# keyboard-8.net
KiCad netlist of a schematic drawn in EAGLE
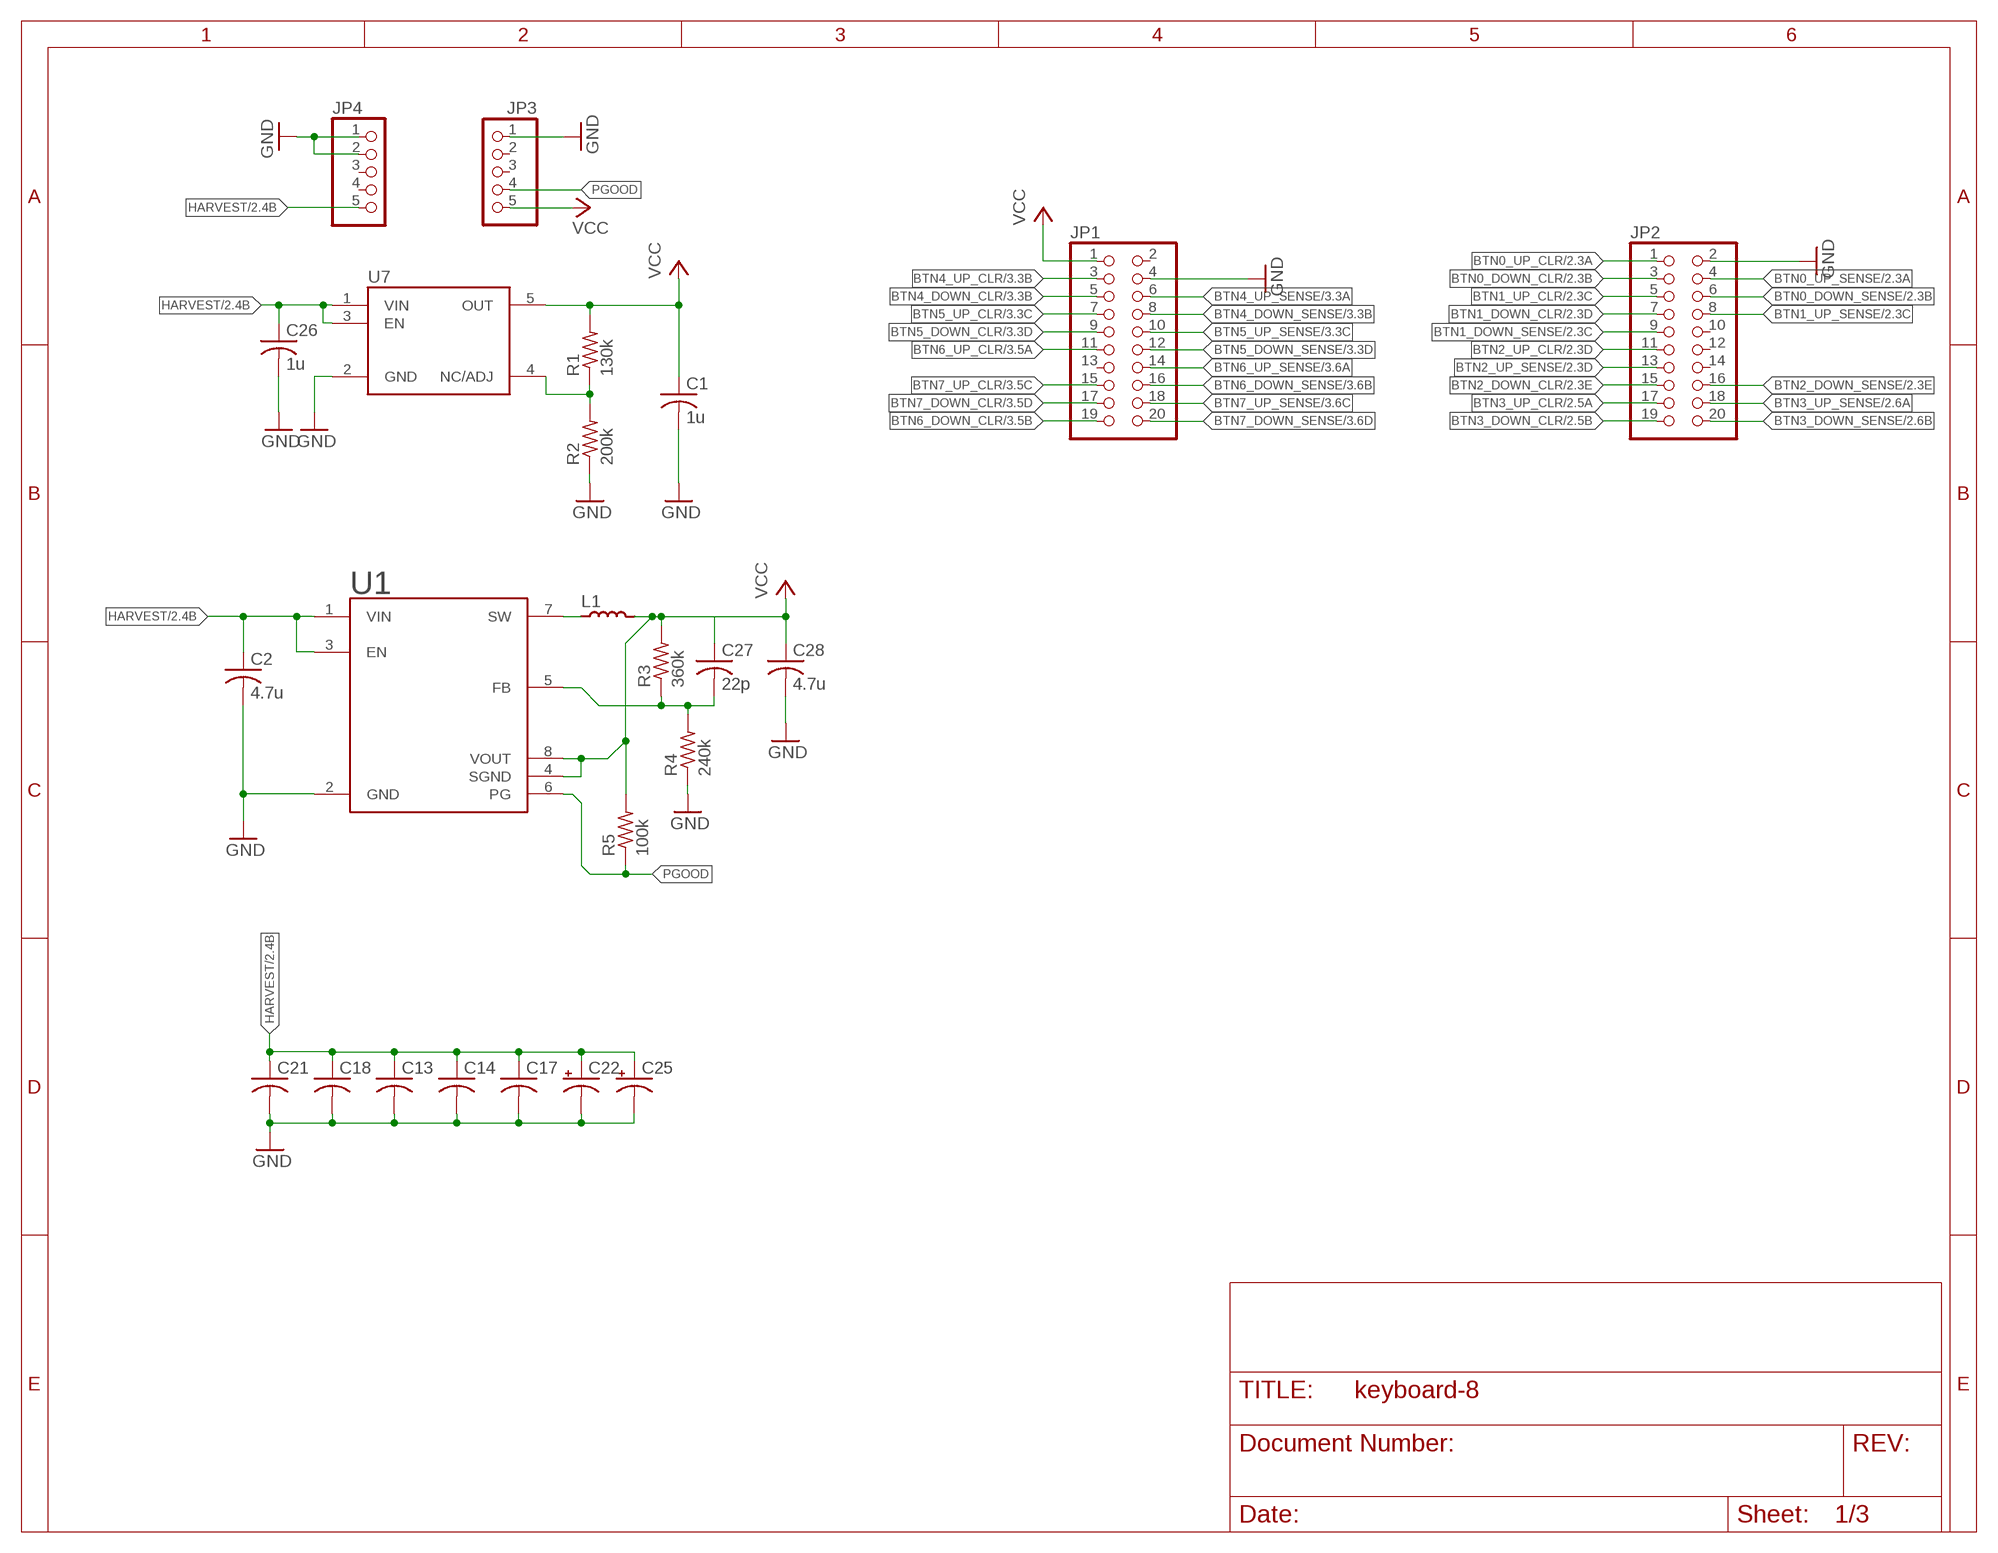
[diagram p0: schematic, sheet 1]
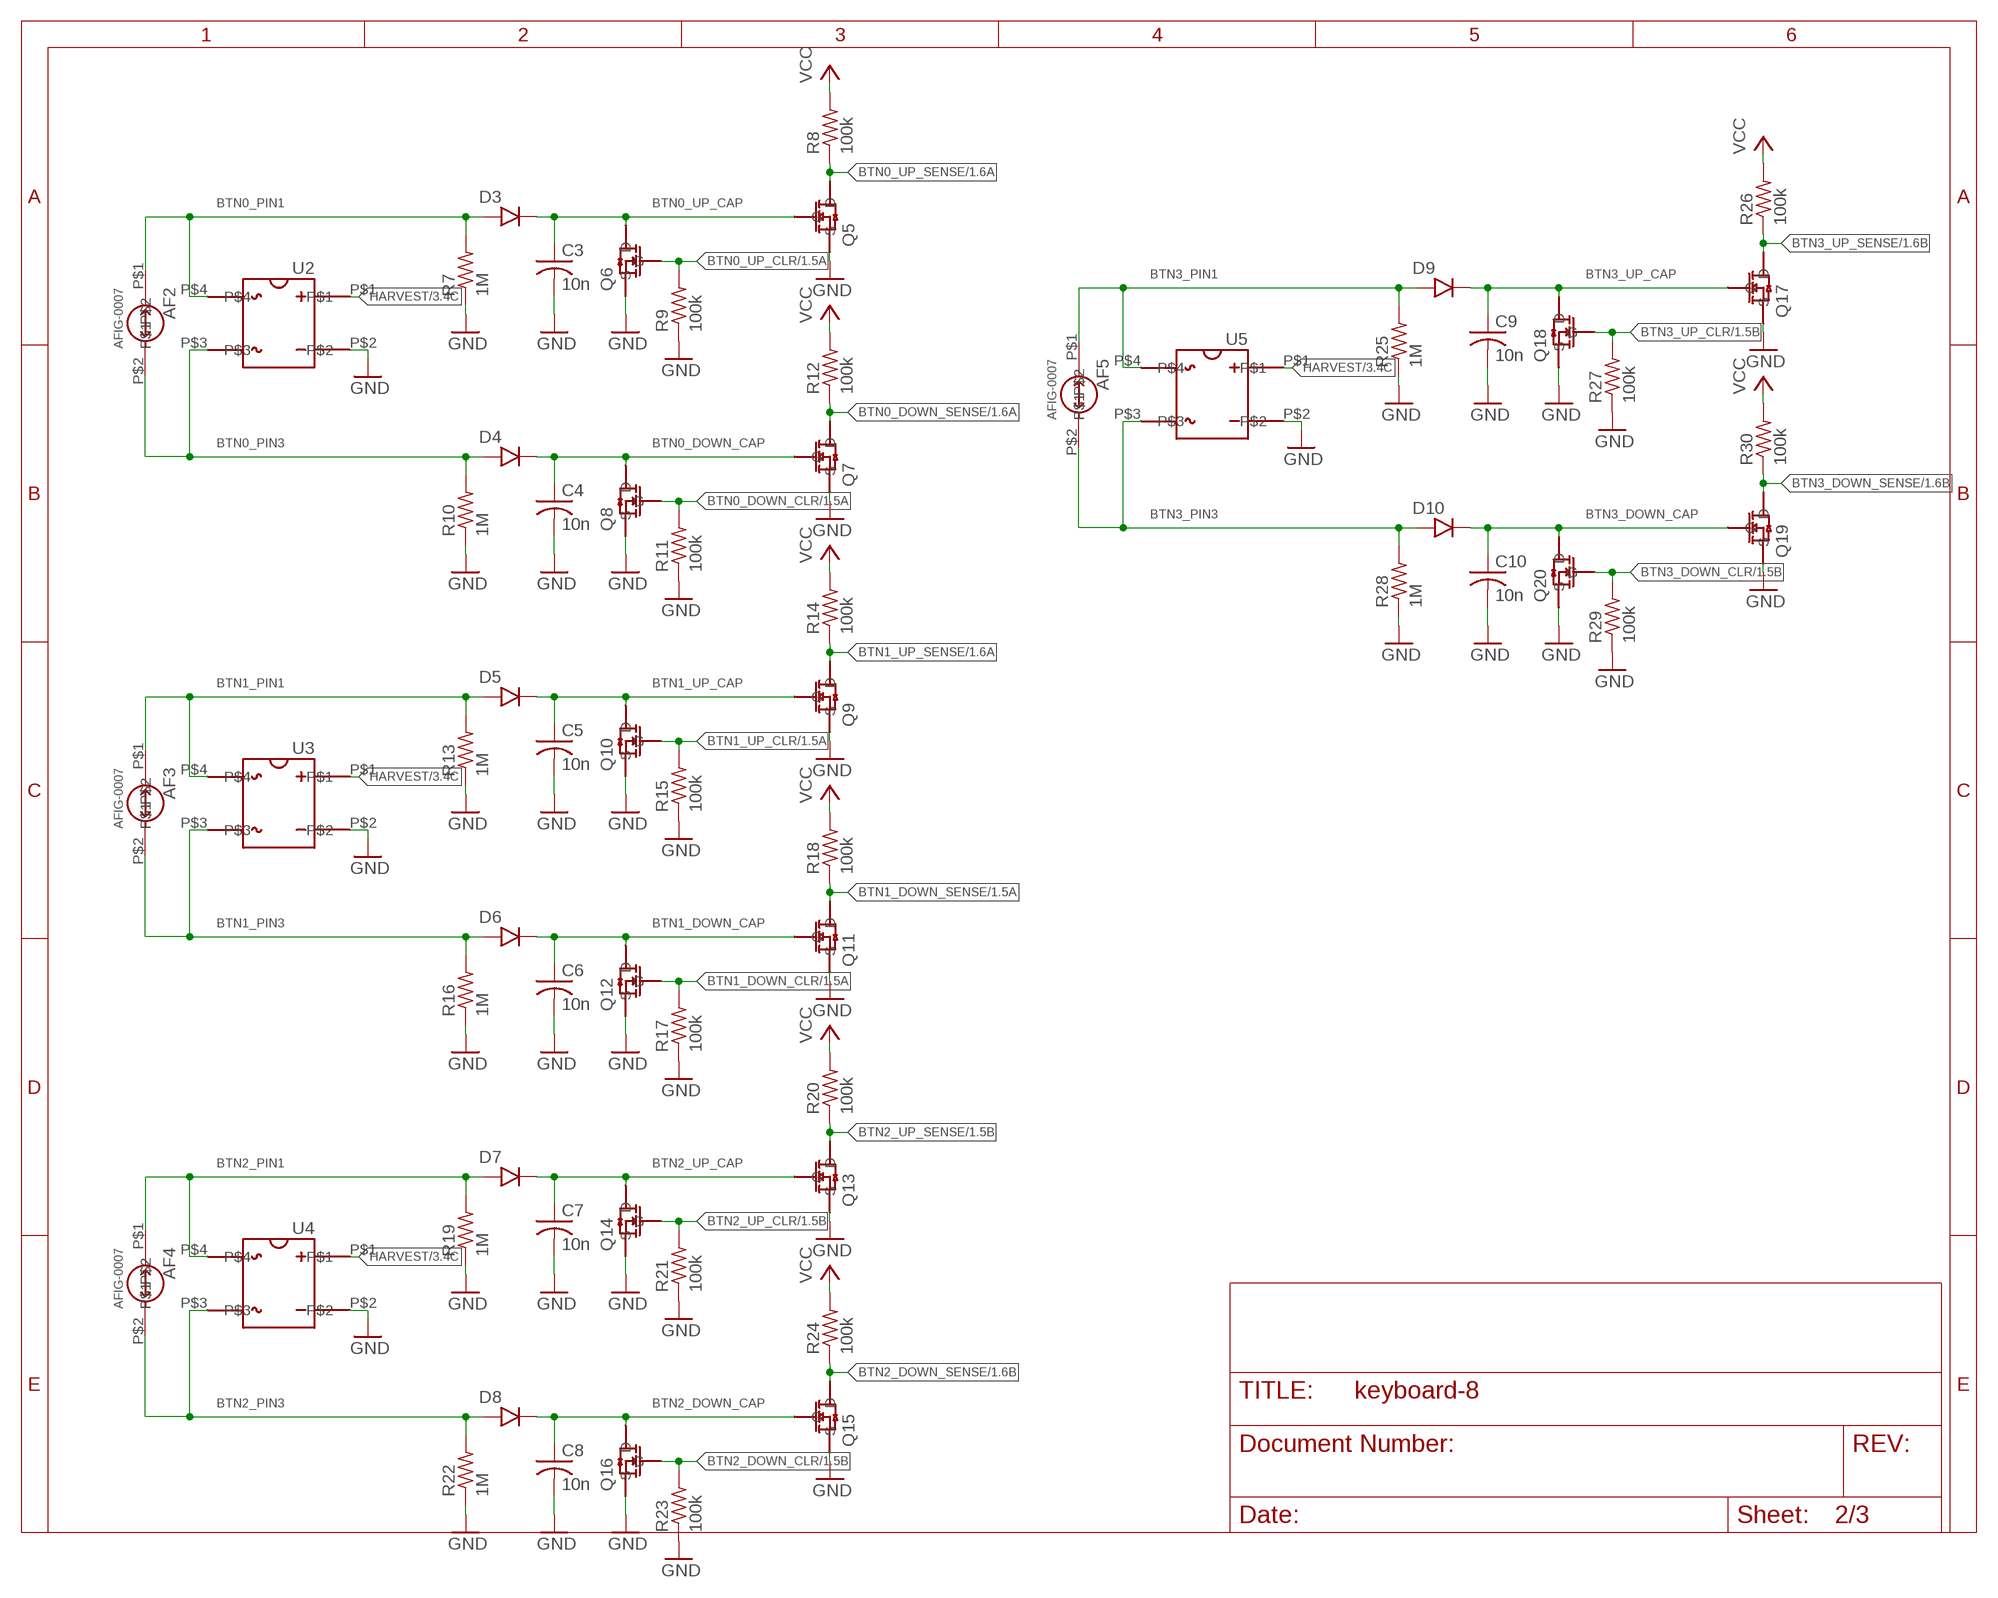
[diagram p1: schematic, sheet 2]
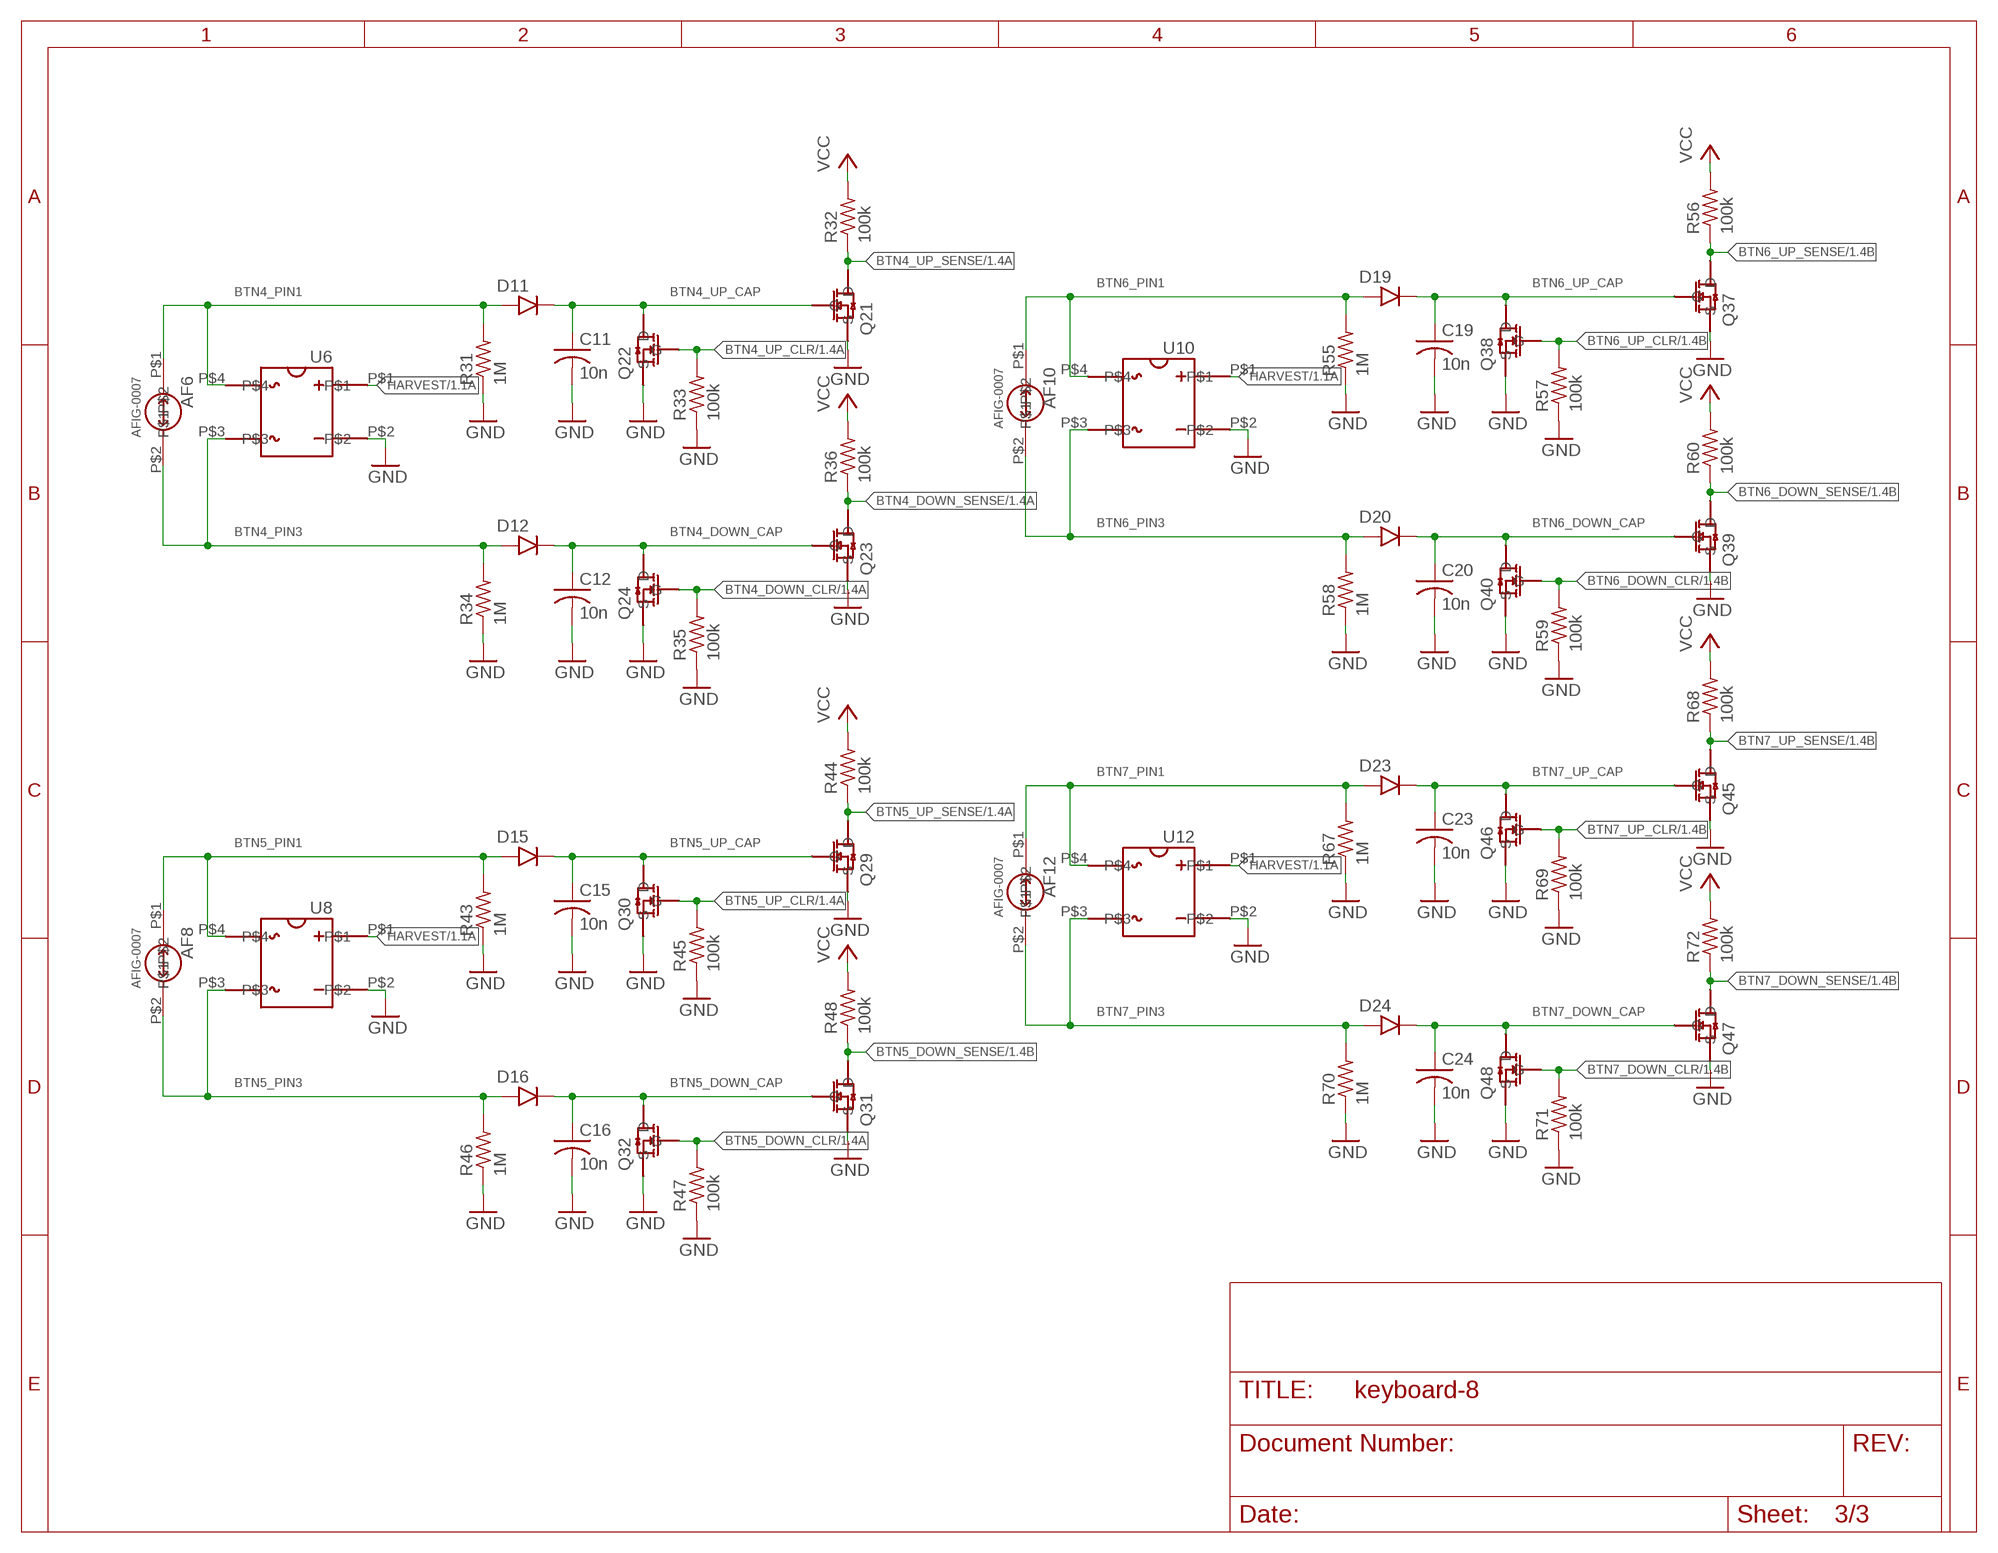
[diagram p2: schematic, sheet 3]

(export (version "E")
  (design (tool "Eeschema 10.0.6"))
  (components
    (comp (ref "C1")
      (value "1u")
      (footprint "eagle-import:C0402")
      (libsource (lib "eagle-import") (part "C-USC0402"))
    )
    (comp (ref "C2")
      (value "4.7u")
      (footprint "eagle-import:C0603")
      (libsource (lib "eagle-import") (part "C-USC0603"))
    )
    (comp (ref "C13")
      (value "C-USC1206")
      (footprint "eagle-import:C1206")
      (libsource (lib "eagle-import") (part "C-USC1206"))
    )
    (comp (ref "C14")
      (value "C-USC1206")
      (footprint "eagle-import:C1206")
      (libsource (lib "eagle-import") (part "C-USC1206"))
    )
    (comp (ref "C17")
      (value "C-USC1206")
      (footprint "eagle-import:C1206")
      (libsource (lib "eagle-import") (part "C-USC1206"))
    )
    (comp (ref "C18")
      (value "C-USC0805")
      (footprint "eagle-import:C0805")
      (libsource (lib "eagle-import") (part "C-USC0805"))
    )
    (comp (ref "C21")
      (value "C-USC0805")
      (footprint "eagle-import:C0805")
      (libsource (lib "eagle-import") (part "C-USC0805"))
    )
    (comp (ref "C22")
      (value "CPOL-USE2-5")
      (footprint "eagle-import:E2-5")
      (libsource (lib "eagle-import") (part "CPOL-USE2-5"))
    )
    (comp (ref "C25")
      (value "CPOL-USE2-5")
      (footprint "eagle-import:E2-5")
      (libsource (lib "eagle-import") (part "CPOL-USE2-5"))
    )
    (comp (ref "C26")
      (value "1u")
      (footprint "eagle-import:C0402")
      (libsource (lib "eagle-import") (part "C-USC0402"))
    )
    (comp (ref "C27")
      (value "22p")
      (footprint "eagle-import:C0402")
      (libsource (lib "eagle-import") (part "C-USC0402"))
    )
    (comp (ref "C28")
      (value "4.7u")
      (footprint "eagle-import:C0603")
      (libsource (lib "eagle-import") (part "C-USC0603"))
    )
    (comp (ref "JP1")
      (value "PINHD-2X10")
      (footprint "eagle-import:2X10")
      (libsource (lib "eagle-import") (part "PINHD-2X10"))
    )
    (comp (ref "JP2")
      (value "PINHD-2X10")
      (footprint "eagle-import:2X10")
      (libsource (lib "eagle-import") (part "PINHD-2X10"))
    )
    (comp (ref "JP3")
      (value "PINHD-1X5")
      (footprint "eagle-import:1X05")
      (libsource (lib "eagle-import") (part "PINHD-1X5"))
    )
    (comp (ref "JP4")
      (value "PINHD-1X5")
      (footprint "eagle-import:1X05")
      (libsource (lib "eagle-import") (part "PINHD-1X5"))
    )
    (comp (ref "L1")
      (value "22u")
      (footprint "eagle-import:LQH3NPNXXXXMEX")
      (libsource (lib "eagle-import") (part "LQH3NPN220MMEL"))
    )
    (comp (ref "R1")
      (value "130k")
      (footprint "eagle-import:R0603")
      (libsource (lib "eagle-import") (part "R-US_R0603"))
    )
    (comp (ref "R2")
      (value "200k")
      (footprint "eagle-import:R0603")
      (libsource (lib "eagle-import") (part "R-US_R0603"))
    )
    (comp (ref "R3")
      (value "360k")
      (footprint "eagle-import:R0402")
      (libsource (lib "eagle-import") (part "R-US_R0402"))
    )
    (comp (ref "R4")
      (value "240k")
      (footprint "eagle-import:R0402")
      (libsource (lib "eagle-import") (part "R-US_R0402"))
    )
    (comp (ref "R5")
      (value "100k")
      (footprint "eagle-import:R0402")
      (libsource (lib "eagle-import") (part "R-US_R0402"))
    )
    (comp (ref "U1")
      (value "TPS62120")
      (footprint "eagle-import:SOP65P280X145-8N")
      (libsource (lib "eagle-import") (part "TPS62120"))
    )
    (comp (ref "U7")
      (value "MIC5225")
      (footprint "eagle-import:MIC5225")
      (libsource (lib "eagle-import") (part "MIC5225"))
    )
    (comp (ref "AF6")
      (value "BUTTON-MOUNT")
      (footprint "eagle-import:BUTTON-MOUNT")
      (libsource (lib "eagle-import") (part "BUTTON-MOUNT"))
    )
    (comp (ref "AF8")
      (value "BUTTON-MOUNT")
      (footprint "eagle-import:BUTTON-MOUNT")
      (libsource (lib "eagle-import") (part "BUTTON-MOUNT"))
    )
    (comp (ref "AF10")
      (value "BUTTON-MOUNT")
      (footprint "eagle-import:BUTTON-MOUNT")
      (libsource (lib "eagle-import") (part "BUTTON-MOUNT"))
    )
    (comp (ref "AF12")
      (value "BUTTON-MOUNT")
      (footprint "eagle-import:BUTTON-MOUNT")
      (libsource (lib "eagle-import") (part "BUTTON-MOUNT"))
    )
    (comp (ref "C11")
      (value "10n")
      (footprint "eagle-import:C0402")
      (libsource (lib "eagle-import") (part "C-USC0402"))
    )
    (comp (ref "C12")
      (value "10n")
      (footprint "eagle-import:C0402")
      (libsource (lib "eagle-import") (part "C-USC0402"))
    )
    (comp (ref "C15")
      (value "10n")
      (footprint "eagle-import:C0402")
      (libsource (lib "eagle-import") (part "C-USC0402"))
    )
    (comp (ref "C16")
      (value "10n")
      (footprint "eagle-import:C0402")
      (libsource (lib "eagle-import") (part "C-USC0402"))
    )
    (comp (ref "C19")
      (value "10n")
      (footprint "eagle-import:C0402")
      (libsource (lib "eagle-import") (part "C-USC0402"))
    )
    (comp (ref "C20")
      (value "10n")
      (footprint "eagle-import:C0402")
      (libsource (lib "eagle-import") (part "C-USC0402"))
    )
    (comp (ref "C23")
      (value "10n")
      (footprint "eagle-import:C0402")
      (libsource (lib "eagle-import") (part "C-USC0402"))
    )
    (comp (ref "C24")
      (value "10n")
      (footprint "eagle-import:C0402")
      (libsource (lib "eagle-import") (part "C-USC0402"))
    )
    (comp (ref "D11")
      (value "DFLU1200")
      (footprint "eagle-import:DFLU1200")
      (libsource (lib "eagle-import") (part "DFLU1200"))
    )
    (comp (ref "D12")
      (value "DFLU1200")
      (footprint "eagle-import:DFLU1200")
      (libsource (lib "eagle-import") (part "DFLU1200"))
    )
    (comp (ref "D15")
      (value "DFLU1200")
      (footprint "eagle-import:DFLU1200")
      (libsource (lib "eagle-import") (part "DFLU1200"))
    )
    (comp (ref "D16")
      (value "DFLU1200")
      (footprint "eagle-import:DFLU1200")
      (libsource (lib "eagle-import") (part "DFLU1200"))
    )
    (comp (ref "D19")
      (value "DFLU1200")
      (footprint "eagle-import:DFLU1200")
      (libsource (lib "eagle-import") (part "DFLU1200"))
    )
    (comp (ref "D20")
      (value "DFLU1200")
      (footprint "eagle-import:DFLU1200")
      (libsource (lib "eagle-import") (part "DFLU1200"))
    )
    (comp (ref "D23")
      (value "DFLU1200")
      (footprint "eagle-import:DFLU1200")
      (libsource (lib "eagle-import") (part "DFLU1200"))
    )
    (comp (ref "D24")
      (value "DFLU1200")
      (footprint "eagle-import:DFLU1200")
      (libsource (lib "eagle-import") (part "DFLU1200"))
    )
    (comp (ref "Q21")
      (value "2N7002K-7")
      (footprint "eagle-import:2N7002K-7")
      (libsource (lib "eagle-import") (part "2N7002K-7"))
    )
    (comp (ref "Q22")
      (value "BSS138K")
      (footprint "eagle-import:BSS138K")
      (libsource (lib "eagle-import") (part "BSS138K"))
    )
    (comp (ref "Q23")
      (value "2N7002K-7")
      (footprint "eagle-import:2N7002K-7")
      (libsource (lib "eagle-import") (part "2N7002K-7"))
    )
    (comp (ref "Q24")
      (value "BSS138K")
      (footprint "eagle-import:BSS138K")
      (libsource (lib "eagle-import") (part "BSS138K"))
    )
    (comp (ref "Q29")
      (value "2N7002K-7")
      (footprint "eagle-import:2N7002K-7")
      (libsource (lib "eagle-import") (part "2N7002K-7"))
    )
    (comp (ref "Q30")
      (value "BSS138K")
      (footprint "eagle-import:BSS138K")
      (libsource (lib "eagle-import") (part "BSS138K"))
    )
    (comp (ref "Q31")
      (value "2N7002K-7")
      (footprint "eagle-import:2N7002K-7")
      (libsource (lib "eagle-import") (part "2N7002K-7"))
    )
    (comp (ref "Q32")
      (value "BSS138K")
      (footprint "eagle-import:BSS138K")
      (libsource (lib "eagle-import") (part "BSS138K"))
    )
    (comp (ref "Q37")
      (value "2N7002K-7")
      (footprint "eagle-import:2N7002K-7")
      (libsource (lib "eagle-import") (part "2N7002K-7"))
    )
    (comp (ref "Q38")
      (value "BSS138K")
      (footprint "eagle-import:BSS138K")
      (libsource (lib "eagle-import") (part "BSS138K"))
    )
    (comp (ref "Q39")
      (value "2N7002K-7")
      (footprint "eagle-import:2N7002K-7")
      (libsource (lib "eagle-import") (part "2N7002K-7"))
    )
    (comp (ref "Q40")
      (value "BSS138K")
      (footprint "eagle-import:BSS138K")
      (libsource (lib "eagle-import") (part "BSS138K"))
    )
    (comp (ref "Q45")
      (value "2N7002K-7")
      (footprint "eagle-import:2N7002K-7")
      (libsource (lib "eagle-import") (part "2N7002K-7"))
    )
    (comp (ref "Q46")
      (value "BSS138K")
      (footprint "eagle-import:BSS138K")
      (libsource (lib "eagle-import") (part "BSS138K"))
    )
    (comp (ref "Q47")
      (value "2N7002K-7")
      (footprint "eagle-import:2N7002K-7")
      (libsource (lib "eagle-import") (part "2N7002K-7"))
    )
    (comp (ref "Q48")
      (value "BSS138K")
      (footprint "eagle-import:BSS138K")
      (libsource (lib "eagle-import") (part "BSS138K"))
    )
    (comp (ref "R31")
      (value "1M")
      (footprint "eagle-import:R0402")
      (libsource (lib "eagle-import") (part "R-US_R0402"))
    )
    (comp (ref "R32")
      (value "100k")
      (footprint "eagle-import:R0402")
      (libsource (lib "eagle-import") (part "R-US_R0402"))
    )
    (comp (ref "R33")
      (value "100k")
      (footprint "eagle-import:R0402")
      (libsource (lib "eagle-import") (part "R-US_R0402"))
    )
    (comp (ref "R34")
      (value "1M")
      (footprint "eagle-import:R0402")
      (libsource (lib "eagle-import") (part "R-US_R0402"))
    )
    (comp (ref "R35")
      (value "100k")
      (footprint "eagle-import:R0402")
      (libsource (lib "eagle-import") (part "R-US_R0402"))
    )
    (comp (ref "R36")
      (value "100k")
      (footprint "eagle-import:R0402")
      (libsource (lib "eagle-import") (part "R-US_R0402"))
    )
    (comp (ref "R43")
      (value "1M")
      (footprint "eagle-import:R0402")
      (libsource (lib "eagle-import") (part "R-US_R0402"))
    )
    (comp (ref "R44")
      (value "100k")
      (footprint "eagle-import:R0402")
      (libsource (lib "eagle-import") (part "R-US_R0402"))
    )
    (comp (ref "R45")
      (value "100k")
      (footprint "eagle-import:R0402")
      (libsource (lib "eagle-import") (part "R-US_R0402"))
    )
    (comp (ref "R46")
      (value "1M")
      (footprint "eagle-import:R0402")
      (libsource (lib "eagle-import") (part "R-US_R0402"))
    )
    (comp (ref "R47")
      (value "100k")
      (footprint "eagle-import:R0402")
      (libsource (lib "eagle-import") (part "R-US_R0402"))
    )
    (comp (ref "R48")
      (value "100k")
      (footprint "eagle-import:R0402")
      (libsource (lib "eagle-import") (part "R-US_R0402"))
    )
    (comp (ref "R55")
      (value "1M")
      (footprint "eagle-import:R0402")
      (libsource (lib "eagle-import") (part "R-US_R0402"))
    )
    (comp (ref "R56")
      (value "100k")
      (footprint "eagle-import:R0402")
      (libsource (lib "eagle-import") (part "R-US_R0402"))
    )
    (comp (ref "R57")
      (value "100k")
      (footprint "eagle-import:R0402")
      (libsource (lib "eagle-import") (part "R-US_R0402"))
    )
    (comp (ref "R58")
      (value "1M")
      (footprint "eagle-import:R0402")
      (libsource (lib "eagle-import") (part "R-US_R0402"))
    )
    (comp (ref "R59")
      (value "100k")
      (footprint "eagle-import:R0402")
      (libsource (lib "eagle-import") (part "R-US_R0402"))
    )
    (comp (ref "R60")
      (value "100k")
      (footprint "eagle-import:R0402")
      (libsource (lib "eagle-import") (part "R-US_R0402"))
    )
    (comp (ref "R67")
      (value "1M")
      (footprint "eagle-import:R0402")
      (libsource (lib "eagle-import") (part "R-US_R0402"))
    )
    (comp (ref "R68")
      (value "100k")
      (footprint "eagle-import:R0402")
      (libsource (lib "eagle-import") (part "R-US_R0402"))
    )
    (comp (ref "R69")
      (value "100k")
      (footprint "eagle-import:R0402")
      (libsource (lib "eagle-import") (part "R-US_R0402"))
    )
    (comp (ref "R70")
      (value "1M")
      (footprint "eagle-import:R0402")
      (libsource (lib "eagle-import") (part "R-US_R0402"))
    )
    (comp (ref "R71")
      (value "100k")
      (footprint "eagle-import:R0402")
      (libsource (lib "eagle-import") (part "R-US_R0402"))
    )
    (comp (ref "R72")
      (value "100k")
      (footprint "eagle-import:R0402")
      (libsource (lib "eagle-import") (part "R-US_R0402"))
    )
    (comp (ref "U6")
      (value "CDBHD140L-G")
      (footprint "eagle-import:CDBHDXX0L-G")
      (libsource (lib "eagle-import") (part "CDBHD140L-G"))
    )
    (comp (ref "U8")
      (value "CDBHD140L-G")
      (footprint "eagle-import:CDBHDXX0L-G")
      (libsource (lib "eagle-import") (part "CDBHD140L-G"))
    )
    (comp (ref "U10")
      (value "CDBHD140L-G")
      (footprint "eagle-import:CDBHDXX0L-G")
      (libsource (lib "eagle-import") (part "CDBHD140L-G"))
    )
    (comp (ref "U12")
      (value "CDBHD140L-G")
      (footprint "eagle-import:CDBHDXX0L-G")
      (libsource (lib "eagle-import") (part "CDBHD140L-G"))
    )
    (comp (ref "AF2")
      (value "BUTTON-MOUNT")
      (footprint "eagle-import:BUTTON-MOUNT")
      (libsource (lib "eagle-import") (part "BUTTON-MOUNT"))
    )
    (comp (ref "AF3")
      (value "BUTTON-MOUNT")
      (footprint "eagle-import:BUTTON-MOUNT")
      (libsource (lib "eagle-import") (part "BUTTON-MOUNT"))
    )
    (comp (ref "AF4")
      (value "BUTTON-MOUNT")
      (footprint "eagle-import:BUTTON-MOUNT")
      (libsource (lib "eagle-import") (part "BUTTON-MOUNT"))
    )
    (comp (ref "AF5")
      (value "BUTTON-MOUNT")
      (footprint "eagle-import:BUTTON-MOUNT")
      (libsource (lib "eagle-import") (part "BUTTON-MOUNT"))
    )
    (comp (ref "C3")
      (value "10n")
      (footprint "eagle-import:C0402")
      (libsource (lib "eagle-import") (part "C-USC0402"))
    )
    (comp (ref "C4")
      (value "10n")
      (footprint "eagle-import:C0402")
      (libsource (lib "eagle-import") (part "C-USC0402"))
    )
    (comp (ref "C5")
      (value "10n")
      (footprint "eagle-import:C0402")
      (libsource (lib "eagle-import") (part "C-USC0402"))
    )
    (comp (ref "C6")
      (value "10n")
      (footprint "eagle-import:C0402")
      (libsource (lib "eagle-import") (part "C-USC0402"))
    )
    (comp (ref "C7")
      (value "10n")
      (footprint "eagle-import:C0402")
      (libsource (lib "eagle-import") (part "C-USC0402"))
    )
    (comp (ref "C8")
      (value "10n")
      (footprint "eagle-import:C0402")
      (libsource (lib "eagle-import") (part "C-USC0402"))
    )
    (comp (ref "C9")
      (value "10n")
      (footprint "eagle-import:C0402")
      (libsource (lib "eagle-import") (part "C-USC0402"))
    )
    (comp (ref "C10")
      (value "10n")
      (footprint "eagle-import:C0402")
      (libsource (lib "eagle-import") (part "C-USC0402"))
    )
    (comp (ref "D3")
      (value "DFLU1200")
      (footprint "eagle-import:DFLU1200")
      (libsource (lib "eagle-import") (part "DFLU1200"))
    )
    (comp (ref "D4")
      (value "DFLU1200")
      (footprint "eagle-import:DFLU1200")
      (libsource (lib "eagle-import") (part "DFLU1200"))
    )
    (comp (ref "D5")
      (value "DFLU1200")
      (footprint "eagle-import:DFLU1200")
      (libsource (lib "eagle-import") (part "DFLU1200"))
    )
    (comp (ref "D6")
      (value "DFLU1200")
      (footprint "eagle-import:DFLU1200")
      (libsource (lib "eagle-import") (part "DFLU1200"))
    )
    (comp (ref "D7")
      (value "DFLU1200")
      (footprint "eagle-import:DFLU1200")
      (libsource (lib "eagle-import") (part "DFLU1200"))
    )
    (comp (ref "D8")
      (value "DFLU1200")
      (footprint "eagle-import:DFLU1200")
      (libsource (lib "eagle-import") (part "DFLU1200"))
    )
    (comp (ref "D9")
      (value "DFLU1200")
      (footprint "eagle-import:DFLU1200")
      (libsource (lib "eagle-import") (part "DFLU1200"))
    )
    (comp (ref "D10")
      (value "DFLU1200")
      (footprint "eagle-import:DFLU1200")
      (libsource (lib "eagle-import") (part "DFLU1200"))
    )
    (comp (ref "Q5")
      (value "2N7002K-7")
      (footprint "eagle-import:2N7002K-7")
      (libsource (lib "eagle-import") (part "2N7002K-7"))
    )
    (comp (ref "Q6")
      (value "BSS138K")
      (footprint "eagle-import:BSS138K")
      (libsource (lib "eagle-import") (part "BSS138K"))
    )
    (comp (ref "Q7")
      (value "2N7002K-7")
      (footprint "eagle-import:2N7002K-7")
      (libsource (lib "eagle-import") (part "2N7002K-7"))
    )
    (comp (ref "Q8")
      (value "BSS138K")
      (footprint "eagle-import:BSS138K")
      (libsource (lib "eagle-import") (part "BSS138K"))
    )
    (comp (ref "Q9")
      (value "2N7002K-7")
      (footprint "eagle-import:2N7002K-7")
      (libsource (lib "eagle-import") (part "2N7002K-7"))
    )
    (comp (ref "Q10")
      (value "BSS138K")
      (footprint "eagle-import:BSS138K")
      (libsource (lib "eagle-import") (part "BSS138K"))
    )
    (comp (ref "Q11")
      (value "2N7002K-7")
      (footprint "eagle-import:2N7002K-7")
      (libsource (lib "eagle-import") (part "2N7002K-7"))
    )
    (comp (ref "Q12")
      (value "BSS138K")
      (footprint "eagle-import:BSS138K")
      (libsource (lib "eagle-import") (part "BSS138K"))
    )
    (comp (ref "Q13")
      (value "2N7002K-7")
      (footprint "eagle-import:2N7002K-7")
      (libsource (lib "eagle-import") (part "2N7002K-7"))
    )
    (comp (ref "Q14")
      (value "BSS138K")
      (footprint "eagle-import:BSS138K")
      (libsource (lib "eagle-import") (part "BSS138K"))
    )
    (comp (ref "Q15")
      (value "2N7002K-7")
      (footprint "eagle-import:2N7002K-7")
      (libsource (lib "eagle-import") (part "2N7002K-7"))
    )
    (comp (ref "Q16")
      (value "BSS138K")
      (footprint "eagle-import:BSS138K")
      (libsource (lib "eagle-import") (part "BSS138K"))
    )
    (comp (ref "Q17")
      (value "2N7002K-7")
      (footprint "eagle-import:2N7002K-7")
      (libsource (lib "eagle-import") (part "2N7002K-7"))
    )
    (comp (ref "Q18")
      (value "BSS138K")
      (footprint "eagle-import:BSS138K")
      (libsource (lib "eagle-import") (part "BSS138K"))
    )
    (comp (ref "Q19")
      (value "2N7002K-7")
      (footprint "eagle-import:2N7002K-7")
      (libsource (lib "eagle-import") (part "2N7002K-7"))
    )
    (comp (ref "Q20")
      (value "BSS138K")
      (footprint "eagle-import:BSS138K")
      (libsource (lib "eagle-import") (part "BSS138K"))
    )
    (comp (ref "R7")
      (value "1M")
      (footprint "eagle-import:R0402")
      (libsource (lib "eagle-import") (part "R-US_R0402"))
    )
    (comp (ref "R8")
      (value "100k")
      (footprint "eagle-import:R0402")
      (libsource (lib "eagle-import") (part "R-US_R0402"))
    )
    (comp (ref "R9")
      (value "100k")
      (footprint "eagle-import:R0402")
      (libsource (lib "eagle-import") (part "R-US_R0402"))
    )
    (comp (ref "R10")
      (value "1M")
      (footprint "eagle-import:R0402")
      (libsource (lib "eagle-import") (part "R-US_R0402"))
    )
    (comp (ref "R11")
      (value "100k")
      (footprint "eagle-import:R0402")
      (libsource (lib "eagle-import") (part "R-US_R0402"))
    )
    (comp (ref "R12")
      (value "100k")
      (footprint "eagle-import:R0402")
      (libsource (lib "eagle-import") (part "R-US_R0402"))
    )
    (comp (ref "R13")
      (value "1M")
      (footprint "eagle-import:R0402")
      (libsource (lib "eagle-import") (part "R-US_R0402"))
    )
    (comp (ref "R14")
      (value "100k")
      (footprint "eagle-import:R0402")
      (libsource (lib "eagle-import") (part "R-US_R0402"))
    )
    (comp (ref "R15")
      (value "100k")
      (footprint "eagle-import:R0402")
      (libsource (lib "eagle-import") (part "R-US_R0402"))
    )
    (comp (ref "R16")
      (value "1M")
      (footprint "eagle-import:R0402")
      (libsource (lib "eagle-import") (part "R-US_R0402"))
    )
    (comp (ref "R17")
      (value "100k")
      (footprint "eagle-import:R0402")
      (libsource (lib "eagle-import") (part "R-US_R0402"))
    )
    (comp (ref "R18")
      (value "100k")
      (footprint "eagle-import:R0402")
      (libsource (lib "eagle-import") (part "R-US_R0402"))
    )
    (comp (ref "R19")
      (value "1M")
      (footprint "eagle-import:R0402")
      (libsource (lib "eagle-import") (part "R-US_R0402"))
    )
    (comp (ref "R20")
      (value "100k")
      (footprint "eagle-import:R0402")
      (libsource (lib "eagle-import") (part "R-US_R0402"))
    )
    (comp (ref "R21")
      (value "100k")
      (footprint "eagle-import:R0402")
      (libsource (lib "eagle-import") (part "R-US_R0402"))
    )
    (comp (ref "R22")
      (value "1M")
      (footprint "eagle-import:R0402")
      (libsource (lib "eagle-import") (part "R-US_R0402"))
    )
    (comp (ref "R23")
      (value "100k")
      (footprint "eagle-import:R0402")
      (libsource (lib "eagle-import") (part "R-US_R0402"))
    )
    (comp (ref "R24")
      (value "100k")
      (footprint "eagle-import:R0402")
      (libsource (lib "eagle-import") (part "R-US_R0402"))
    )
    (comp (ref "R25")
      (value "1M")
      (footprint "eagle-import:R0402")
      (libsource (lib "eagle-import") (part "R-US_R0402"))
    )
    (comp (ref "R26")
      (value "100k")
      (footprint "eagle-import:R0402")
      (libsource (lib "eagle-import") (part "R-US_R0402"))
    )
    (comp (ref "R27")
      (value "100k")
      (footprint "eagle-import:R0402")
      (libsource (lib "eagle-import") (part "R-US_R0402"))
    )
    (comp (ref "R28")
      (value "1M")
      (footprint "eagle-import:R0402")
      (libsource (lib "eagle-import") (part "R-US_R0402"))
    )
    (comp (ref "R29")
      (value "100k")
      (footprint "eagle-import:R0402")
      (libsource (lib "eagle-import") (part "R-US_R0402"))
    )
    (comp (ref "R30")
      (value "100k")
      (footprint "eagle-import:R0402")
      (libsource (lib "eagle-import") (part "R-US_R0402"))
    )
    (comp (ref "U2")
      (value "CDBHD140L-G")
      (footprint "eagle-import:CDBHDXX0L-G")
      (libsource (lib "eagle-import") (part "CDBHD140L-G"))
    )
    (comp (ref "U3")
      (value "CDBHD140L-G")
      (footprint "eagle-import:CDBHDXX0L-G")
      (libsource (lib "eagle-import") (part "CDBHD140L-G"))
    )
    (comp (ref "U4")
      (value "CDBHD140L-G")
      (footprint "eagle-import:CDBHDXX0L-G")
      (libsource (lib "eagle-import") (part "CDBHD140L-G"))
    )
    (comp (ref "U5")
      (value "CDBHD140L-G")
      (footprint "eagle-import:CDBHDXX0L-G")
      (libsource (lib "eagle-import") (part "CDBHD140L-G"))
    )
  )
  (nets
    (net (code "1") (name "BTN0_DOWN_CAP") (class "Default")
      (node (ref "C4") (pin "1") (pinfunction "1_1") (pintype "passive"))
      (node (ref "D4") (pin "K") (pinfunction "K_K") (pintype "bidirectional"))
      (node (ref "Q7") (pin "G") (pinfunction "G_G") (pintype "bidirectional"))
      (node (ref "Q8") (pin "D") (pinfunction "D_D") (pintype "bidirectional"))
    )
    (net (code "2") (name "BTN0_DOWN_CLR") (class "Default")
      (node (ref "JP2") (pin "3") (pinfunction "3_3") (pintype "passive"))
      (node (ref "Q8") (pin "G") (pinfunction "G_G") (pintype "bidirectional"))
      (node (ref "R11") (pin "2") (pinfunction "2_2") (pintype "passive"))
    )
    (net (code "3") (name "BTN0_DOWN_SENSE") (class "Default")
      (node (ref "JP2") (pin "6") (pinfunction "6_6") (pintype "passive"))
      (node (ref "Q7") (pin "D") (pinfunction "D_D") (pintype "bidirectional"))
      (node (ref "R12") (pin "1") (pinfunction "1_1") (pintype "passive"))
    )
    (net (code "4") (name "BTN0_PIN1") (class "Default")
      (node (ref "AF2") (pin "P$1") (pinfunction "P$1_P$1") (pintype "bidirectional"))
      (node (ref "D3") (pin "A") (pinfunction "A_A") (pintype "bidirectional"))
      (node (ref "R7") (pin "2") (pinfunction "2_2") (pintype "passive"))
      (node (ref "U2") (pin "P$4") (pinfunction "P$4_P$4") (pintype "bidirectional"))
    )
    (net (code "5") (name "BTN0_PIN3") (class "Default")
      (node (ref "AF2") (pin "P$2") (pinfunction "P$2_P$2") (pintype "bidirectional"))
      (node (ref "D4") (pin "A") (pinfunction "A_A") (pintype "bidirectional"))
      (node (ref "R10") (pin "2") (pinfunction "2_2") (pintype "passive"))
      (node (ref "U2") (pin "P$3") (pinfunction "P$3_P$3") (pintype "bidirectional"))
    )
    (net (code "6") (name "BTN0_UP_CAP") (class "Default")
      (node (ref "C3") (pin "1") (pinfunction "1_1") (pintype "passive"))
      (node (ref "D3") (pin "K") (pinfunction "K_K") (pintype "bidirectional"))
      (node (ref "Q5") (pin "G") (pinfunction "G_G") (pintype "bidirectional"))
      (node (ref "Q6") (pin "D") (pinfunction "D_D") (pintype "bidirectional"))
    )
    (net (code "7") (name "BTN0_UP_CLR") (class "Default")
      (node (ref "JP2") (pin "1") (pinfunction "1_1") (pintype "passive"))
      (node (ref "Q6") (pin "G") (pinfunction "G_G") (pintype "bidirectional"))
      (node (ref "R9") (pin "2") (pinfunction "2_2") (pintype "passive"))
    )
    (net (code "8") (name "BTN0_UP_SENSE") (class "Default")
      (node (ref "JP2") (pin "4") (pinfunction "4_4") (pintype "passive"))
      (node (ref "Q5") (pin "D") (pinfunction "D_D") (pintype "bidirectional"))
      (node (ref "R8") (pin "1") (pinfunction "1_1") (pintype "passive"))
    )
    (net (code "9") (name "BTN1_DOWN_CAP") (class "Default")
      (node (ref "C6") (pin "1") (pinfunction "1_1") (pintype "passive"))
      (node (ref "D6") (pin "K") (pinfunction "K_K") (pintype "bidirectional"))
      (node (ref "Q11") (pin "G") (pinfunction "G_G") (pintype "bidirectional"))
      (node (ref "Q12") (pin "D") (pinfunction "D_D") (pintype "bidirectional"))
    )
    (net (code "10") (name "BTN1_DOWN_CLR") (class "Default")
      (node (ref "JP2") (pin "7") (pinfunction "7_7") (pintype "passive"))
      (node (ref "Q12") (pin "G") (pinfunction "G_G") (pintype "bidirectional"))
      (node (ref "R17") (pin "2") (pinfunction "2_2") (pintype "passive"))
    )
    (net (code "11") (name "BTN1_DOWN_SENSE") (class "Default")
      (node (ref "JP2") (pin "9") (pinfunction "9_9") (pintype "passive"))
      (node (ref "Q11") (pin "D") (pinfunction "D_D") (pintype "bidirectional"))
      (node (ref "R18") (pin "1") (pinfunction "1_1") (pintype "passive"))
    )
    (net (code "12") (name "BTN1_PIN1") (class "Default")
      (node (ref "AF3") (pin "P$1") (pinfunction "P$1_P$1") (pintype "bidirectional"))
      (node (ref "D5") (pin "A") (pinfunction "A_A") (pintype "bidirectional"))
      (node (ref "R13") (pin "2") (pinfunction "2_2") (pintype "passive"))
      (node (ref "U3") (pin "P$4") (pinfunction "P$4_P$4") (pintype "bidirectional"))
    )
    (net (code "13") (name "BTN1_PIN3") (class "Default")
      (node (ref "AF3") (pin "P$2") (pinfunction "P$2_P$2") (pintype "bidirectional"))
      (node (ref "D6") (pin "A") (pinfunction "A_A") (pintype "bidirectional"))
      (node (ref "R16") (pin "2") (pinfunction "2_2") (pintype "passive"))
      (node (ref "U3") (pin "P$3") (pinfunction "P$3_P$3") (pintype "bidirectional"))
    )
    (net (code "14") (name "BTN1_UP_CAP") (class "Default")
      (node (ref "C5") (pin "1") (pinfunction "1_1") (pintype "passive"))
      (node (ref "D5") (pin "K") (pinfunction "K_K") (pintype "bidirectional"))
      (node (ref "Q10") (pin "D") (pinfunction "D_D") (pintype "bidirectional"))
      (node (ref "Q9") (pin "G") (pinfunction "G_G") (pintype "bidirectional"))
    )
    (net (code "15") (name "BTN1_UP_CLR") (class "Default")
      (node (ref "JP2") (pin "5") (pinfunction "5_5") (pintype "passive"))
      (node (ref "Q10") (pin "G") (pinfunction "G_G") (pintype "bidirectional"))
      (node (ref "R15") (pin "2") (pinfunction "2_2") (pintype "passive"))
    )
    (net (code "16") (name "BTN1_UP_SENSE") (class "Default")
      (node (ref "JP2") (pin "8") (pinfunction "8_8") (pintype "passive"))
      (node (ref "Q9") (pin "D") (pinfunction "D_D") (pintype "bidirectional"))
      (node (ref "R14") (pin "1") (pinfunction "1_1") (pintype "passive"))
    )
    (net (code "17") (name "BTN2_DOWN_CAP") (class "Default")
      (node (ref "C8") (pin "1") (pinfunction "1_1") (pintype "passive"))
      (node (ref "D8") (pin "K") (pinfunction "K_K") (pintype "bidirectional"))
      (node (ref "Q15") (pin "G") (pinfunction "G_G") (pintype "bidirectional"))
      (node (ref "Q16") (pin "D") (pinfunction "D_D") (pintype "bidirectional"))
    )
    (net (code "18") (name "BTN2_DOWN_CLR") (class "Default")
      (node (ref "JP2") (pin "15") (pinfunction "15_15") (pintype "passive"))
      (node (ref "Q16") (pin "G") (pinfunction "G_G") (pintype "bidirectional"))
      (node (ref "R23") (pin "2") (pinfunction "2_2") (pintype "passive"))
    )
    (net (code "19") (name "BTN2_DOWN_SENSE") (class "Default")
      (node (ref "JP2") (pin "16") (pinfunction "16_16") (pintype "passive"))
      (node (ref "Q15") (pin "D") (pinfunction "D_D") (pintype "bidirectional"))
      (node (ref "R24") (pin "1") (pinfunction "1_1") (pintype "passive"))
    )
    (net (code "20") (name "BTN2_PIN1") (class "Default")
      (node (ref "AF4") (pin "P$1") (pinfunction "P$1_P$1") (pintype "bidirectional"))
      (node (ref "D7") (pin "A") (pinfunction "A_A") (pintype "bidirectional"))
      (node (ref "R19") (pin "2") (pinfunction "2_2") (pintype "passive"))
      (node (ref "U4") (pin "P$4") (pinfunction "P$4_P$4") (pintype "bidirectional"))
    )
    (net (code "21") (name "BTN2_PIN3") (class "Default")
      (node (ref "AF4") (pin "P$2") (pinfunction "P$2_P$2") (pintype "bidirectional"))
      (node (ref "D8") (pin "A") (pinfunction "A_A") (pintype "bidirectional"))
      (node (ref "R22") (pin "2") (pinfunction "2_2") (pintype "passive"))
      (node (ref "U4") (pin "P$3") (pinfunction "P$3_P$3") (pintype "bidirectional"))
    )
    (net (code "22") (name "BTN2_UP_CAP") (class "Default")
      (node (ref "C7") (pin "1") (pinfunction "1_1") (pintype "passive"))
      (node (ref "D7") (pin "K") (pinfunction "K_K") (pintype "bidirectional"))
      (node (ref "Q13") (pin "G") (pinfunction "G_G") (pintype "bidirectional"))
      (node (ref "Q14") (pin "D") (pinfunction "D_D") (pintype "bidirectional"))
    )
    (net (code "23") (name "BTN2_UP_CLR") (class "Default")
      (node (ref "JP2") (pin "11") (pinfunction "11_11") (pintype "passive"))
      (node (ref "Q14") (pin "G") (pinfunction "G_G") (pintype "bidirectional"))
      (node (ref "R21") (pin "2") (pinfunction "2_2") (pintype "passive"))
    )
    (net (code "24") (name "BTN2_UP_SENSE") (class "Default")
      (node (ref "JP2") (pin "13") (pinfunction "13_13") (pintype "passive"))
      (node (ref "Q13") (pin "D") (pinfunction "D_D") (pintype "bidirectional"))
      (node (ref "R20") (pin "1") (pinfunction "1_1") (pintype "passive"))
    )
    (net (code "25") (name "BTN3_DOWN_CAP") (class "Default")
      (node (ref "C10") (pin "1") (pinfunction "1_1") (pintype "passive"))
      (node (ref "D10") (pin "K") (pinfunction "K_K") (pintype "bidirectional"))
      (node (ref "Q19") (pin "G") (pinfunction "G_G") (pintype "bidirectional"))
      (node (ref "Q20") (pin "D") (pinfunction "D_D") (pintype "bidirectional"))
    )
    (net (code "26") (name "BTN3_DOWN_CLR") (class "Default")
      (node (ref "JP2") (pin "19") (pinfunction "19_19") (pintype "passive"))
      (node (ref "Q20") (pin "G") (pinfunction "G_G") (pintype "bidirectional"))
      (node (ref "R29") (pin "2") (pinfunction "2_2") (pintype "passive"))
    )
    (net (code "27") (name "BTN3_DOWN_SENSE") (class "Default")
      (node (ref "JP2") (pin "20") (pinfunction "20_20") (pintype "passive"))
      (node (ref "Q19") (pin "D") (pinfunction "D_D") (pintype "bidirectional"))
      (node (ref "R30") (pin "1") (pinfunction "1_1") (pintype "passive"))
    )
    (net (code "28") (name "BTN3_PIN1") (class "Default")
      (node (ref "AF5") (pin "P$1") (pinfunction "P$1_P$1") (pintype "bidirectional"))
      (node (ref "D9") (pin "A") (pinfunction "A_A") (pintype "bidirectional"))
      (node (ref "R25") (pin "2") (pinfunction "2_2") (pintype "passive"))
      (node (ref "U5") (pin "P$4") (pinfunction "P$4_P$4") (pintype "bidirectional"))
    )
    (net (code "29") (name "BTN3_PIN3") (class "Default")
      (node (ref "AF5") (pin "P$2") (pinfunction "P$2_P$2") (pintype "bidirectional"))
      (node (ref "D10") (pin "A") (pinfunction "A_A") (pintype "bidirectional"))
      (node (ref "R28") (pin "2") (pinfunction "2_2") (pintype "passive"))
      (node (ref "U5") (pin "P$3") (pinfunction "P$3_P$3") (pintype "bidirectional"))
    )
    (net (code "30") (name "BTN3_UP_CAP") (class "Default")
      (node (ref "C9") (pin "1") (pinfunction "1_1") (pintype "passive"))
      (node (ref "D9") (pin "K") (pinfunction "K_K") (pintype "bidirectional"))
      (node (ref "Q17") (pin "G") (pinfunction "G_G") (pintype "bidirectional"))
      (node (ref "Q18") (pin "D") (pinfunction "D_D") (pintype "bidirectional"))
    )
    (net (code "31") (name "BTN3_UP_CLR") (class "Default")
      (node (ref "JP2") (pin "17") (pinfunction "17_17") (pintype "passive"))
      (node (ref "Q18") (pin "G") (pinfunction "G_G") (pintype "bidirectional"))
      (node (ref "R27") (pin "2") (pinfunction "2_2") (pintype "passive"))
    )
    (net (code "32") (name "BTN3_UP_SENSE") (class "Default")
      (node (ref "JP2") (pin "18") (pinfunction "18_18") (pintype "passive"))
      (node (ref "Q17") (pin "D") (pinfunction "D_D") (pintype "bidirectional"))
      (node (ref "R26") (pin "1") (pinfunction "1_1") (pintype "passive"))
    )
    (net (code "33") (name "BTN4_DOWN_CAP") (class "Default")
      (node (ref "C12") (pin "1") (pinfunction "1_1") (pintype "passive"))
      (node (ref "D12") (pin "K") (pinfunction "K_K") (pintype "bidirectional"))
      (node (ref "Q23") (pin "G") (pinfunction "G_G") (pintype "bidirectional"))
      (node (ref "Q24") (pin "D") (pinfunction "D_D") (pintype "bidirectional"))
    )
    (net (code "34") (name "BTN4_DOWN_CLR") (class "Default")
      (node (ref "JP1") (pin "5") (pinfunction "5_5") (pintype "passive"))
      (node (ref "Q24") (pin "G") (pinfunction "G_G") (pintype "bidirectional"))
      (node (ref "R35") (pin "2") (pinfunction "2_2") (pintype "passive"))
    )
    (net (code "35") (name "BTN4_DOWN_SENSE") (class "Default")
      (node (ref "JP1") (pin "8") (pinfunction "8_8") (pintype "passive"))
      (node (ref "Q23") (pin "D") (pinfunction "D_D") (pintype "bidirectional"))
      (node (ref "R36") (pin "1") (pinfunction "1_1") (pintype "passive"))
    )
    (net (code "36") (name "BTN4_PIN1") (class "Default")
      (node (ref "AF6") (pin "P$1") (pinfunction "P$1_P$1") (pintype "bidirectional"))
      (node (ref "D11") (pin "A") (pinfunction "A_A") (pintype "bidirectional"))
      (node (ref "R31") (pin "2") (pinfunction "2_2") (pintype "passive"))
      (node (ref "U6") (pin "P$4") (pinfunction "P$4_P$4") (pintype "bidirectional"))
    )
    (net (code "37") (name "BTN4_PIN3") (class "Default")
      (node (ref "AF6") (pin "P$2") (pinfunction "P$2_P$2") (pintype "bidirectional"))
      (node (ref "D12") (pin "A") (pinfunction "A_A") (pintype "bidirectional"))
      (node (ref "R34") (pin "2") (pinfunction "2_2") (pintype "passive"))
      (node (ref "U6") (pin "P$3") (pinfunction "P$3_P$3") (pintype "bidirectional"))
    )
    (net (code "38") (name "BTN4_UP_CAP") (class "Default")
      (node (ref "C11") (pin "1") (pinfunction "1_1") (pintype "passive"))
      (node (ref "D11") (pin "K") (pinfunction "K_K") (pintype "bidirectional"))
      (node (ref "Q21") (pin "G") (pinfunction "G_G") (pintype "bidirectional"))
      (node (ref "Q22") (pin "D") (pinfunction "D_D") (pintype "bidirectional"))
    )
    (net (code "39") (name "BTN4_UP_CLR") (class "Default")
      (node (ref "JP1") (pin "3") (pinfunction "3_3") (pintype "passive"))
      (node (ref "Q22") (pin "G") (pinfunction "G_G") (pintype "bidirectional"))
      (node (ref "R33") (pin "2") (pinfunction "2_2") (pintype "passive"))
    )
    (net (code "40") (name "BTN4_UP_SENSE") (class "Default")
      (node (ref "JP1") (pin "6") (pinfunction "6_6") (pintype "passive"))
      (node (ref "Q21") (pin "D") (pinfunction "D_D") (pintype "bidirectional"))
      (node (ref "R32") (pin "1") (pinfunction "1_1") (pintype "passive"))
    )
    (net (code "41") (name "BTN5_DOWN_CAP") (class "Default")
      (node (ref "C16") (pin "1") (pinfunction "1_1") (pintype "passive"))
      (node (ref "D16") (pin "K") (pinfunction "K_K") (pintype "bidirectional"))
      (node (ref "Q31") (pin "G") (pinfunction "G_G") (pintype "bidirectional"))
      (node (ref "Q32") (pin "D") (pinfunction "D_D") (pintype "bidirectional"))
    )
    (net (code "42") (name "BTN5_DOWN_CLR") (class "Default")
      (node (ref "JP1") (pin "9") (pinfunction "9_9") (pintype "passive"))
      (node (ref "Q32") (pin "G") (pinfunction "G_G") (pintype "bidirectional"))
      (node (ref "R47") (pin "2") (pinfunction "2_2") (pintype "passive"))
    )
    (net (code "43") (name "BTN5_DOWN_SENSE") (class "Default")
      (node (ref "JP1") (pin "12") (pinfunction "12_12") (pintype "passive"))
      (node (ref "Q31") (pin "D") (pinfunction "D_D") (pintype "bidirectional"))
      (node (ref "R48") (pin "1") (pinfunction "1_1") (pintype "passive"))
    )
    (net (code "44") (name "BTN5_PIN1") (class "Default")
      (node (ref "AF8") (pin "P$1") (pinfunction "P$1_P$1") (pintype "bidirectional"))
      (node (ref "D15") (pin "A") (pinfunction "A_A") (pintype "bidirectional"))
      (node (ref "R43") (pin "2") (pinfunction "2_2") (pintype "passive"))
      (node (ref "U8") (pin "P$4") (pinfunction "P$4_P$4") (pintype "bidirectional"))
    )
    (net (code "45") (name "BTN5_PIN3") (class "Default")
      (node (ref "AF8") (pin "P$2") (pinfunction "P$2_P$2") (pintype "bidirectional"))
      (node (ref "D16") (pin "A") (pinfunction "A_A") (pintype "bidirectional"))
      (node (ref "R46") (pin "2") (pinfunction "2_2") (pintype "passive"))
      (node (ref "U8") (pin "P$3") (pinfunction "P$3_P$3") (pintype "bidirectional"))
    )
    (net (code "46") (name "BTN5_UP_CAP") (class "Default")
      (node (ref "C15") (pin "1") (pinfunction "1_1") (pintype "passive"))
      (node (ref "D15") (pin "K") (pinfunction "K_K") (pintype "bidirectional"))
      (node (ref "Q29") (pin "G") (pinfunction "G_G") (pintype "bidirectional"))
      (node (ref "Q30") (pin "D") (pinfunction "D_D") (pintype "bidirectional"))
    )
    (net (code "47") (name "BTN5_UP_CLR") (class "Default")
      (node (ref "JP1") (pin "7") (pinfunction "7_7") (pintype "passive"))
      (node (ref "Q30") (pin "G") (pinfunction "G_G") (pintype "bidirectional"))
      (node (ref "R45") (pin "2") (pinfunction "2_2") (pintype "passive"))
    )
    (net (code "48") (name "BTN5_UP_SENSE") (class "Default")
      (node (ref "JP1") (pin "10") (pinfunction "10_10") (pintype "passive"))
      (node (ref "Q29") (pin "D") (pinfunction "D_D") (pintype "bidirectional"))
      (node (ref "R44") (pin "1") (pinfunction "1_1") (pintype "passive"))
    )
    (net (code "49") (name "BTN6_DOWN_CAP") (class "Default")
      (node (ref "C20") (pin "1") (pinfunction "1_1") (pintype "passive"))
      (node (ref "D20") (pin "K") (pinfunction "K_K") (pintype "bidirectional"))
      (node (ref "Q39") (pin "G") (pinfunction "G_G") (pintype "bidirectional"))
      (node (ref "Q40") (pin "D") (pinfunction "D_D") (pintype "bidirectional"))
    )
    (net (code "50") (name "BTN6_DOWN_CLR") (class "Default")
      (node (ref "JP1") (pin "19") (pinfunction "19_19") (pintype "passive"))
      (node (ref "Q40") (pin "G") (pinfunction "G_G") (pintype "bidirectional"))
      (node (ref "R59") (pin "2") (pinfunction "2_2") (pintype "passive"))
    )
    (net (code "51") (name "BTN6_DOWN_SENSE") (class "Default")
      (node (ref "JP1") (pin "16") (pinfunction "16_16") (pintype "passive"))
      (node (ref "Q39") (pin "D") (pinfunction "D_D") (pintype "bidirectional"))
      (node (ref "R60") (pin "1") (pinfunction "1_1") (pintype "passive"))
    )
    (net (code "52") (name "BTN6_PIN1") (class "Default")
      (node (ref "AF10") (pin "P$1") (pinfunction "P$1_P$1") (pintype "bidirectional"))
      (node (ref "D19") (pin "A") (pinfunction "A_A") (pintype "bidirectional"))
      (node (ref "R55") (pin "2") (pinfunction "2_2") (pintype "passive"))
      (node (ref "U10") (pin "P$4") (pinfunction "P$4_P$4") (pintype "bidirectional"))
    )
    (net (code "53") (name "BTN6_PIN3") (class "Default")
      (node (ref "AF10") (pin "P$2") (pinfunction "P$2_P$2") (pintype "bidirectional"))
      (node (ref "D20") (pin "A") (pinfunction "A_A") (pintype "bidirectional"))
      (node (ref "R58") (pin "2") (pinfunction "2_2") (pintype "passive"))
      (node (ref "U10") (pin "P$3") (pinfunction "P$3_P$3") (pintype "bidirectional"))
    )
    (net (code "54") (name "BTN6_UP_CAP") (class "Default")
      (node (ref "C19") (pin "1") (pinfunction "1_1") (pintype "passive"))
      (node (ref "D19") (pin "K") (pinfunction "K_K") (pintype "bidirectional"))
      (node (ref "Q37") (pin "G") (pinfunction "G_G") (pintype "bidirectional"))
      (node (ref "Q38") (pin "D") (pinfunction "D_D") (pintype "bidirectional"))
    )
    (net (code "55") (name "BTN6_UP_CLR") (class "Default")
      (node (ref "JP1") (pin "11") (pinfunction "11_11") (pintype "passive"))
      (node (ref "Q38") (pin "G") (pinfunction "G_G") (pintype "bidirectional"))
      (node (ref "R57") (pin "2") (pinfunction "2_2") (pintype "passive"))
    )
    (net (code "56") (name "BTN6_UP_SENSE") (class "Default")
      (node (ref "JP1") (pin "14") (pinfunction "14_14") (pintype "passive"))
      (node (ref "Q37") (pin "D") (pinfunction "D_D") (pintype "bidirectional"))
      (node (ref "R56") (pin "1") (pinfunction "1_1") (pintype "passive"))
    )
    (net (code "57") (name "BTN7_DOWN_CAP") (class "Default")
      (node (ref "C24") (pin "1") (pinfunction "1_1") (pintype "passive"))
      (node (ref "D24") (pin "K") (pinfunction "K_K") (pintype "bidirectional"))
      (node (ref "Q47") (pin "G") (pinfunction "G_G") (pintype "bidirectional"))
      (node (ref "Q48") (pin "D") (pinfunction "D_D") (pintype "bidirectional"))
    )
    (net (code "58") (name "BTN7_DOWN_CLR") (class "Default")
      (node (ref "JP1") (pin "17") (pinfunction "17_17") (pintype "passive"))
      (node (ref "Q48") (pin "G") (pinfunction "G_G") (pintype "bidirectional"))
      (node (ref "R71") (pin "2") (pinfunction "2_2") (pintype "passive"))
    )
    (net (code "59") (name "BTN7_DOWN_SENSE") (class "Default")
      (node (ref "JP1") (pin "20") (pinfunction "20_20") (pintype "passive"))
      (node (ref "Q47") (pin "D") (pinfunction "D_D") (pintype "bidirectional"))
      (node (ref "R72") (pin "1") (pinfunction "1_1") (pintype "passive"))
    )
    (net (code "60") (name "BTN7_PIN1") (class "Default")
      (node (ref "AF12") (pin "P$1") (pinfunction "P$1_P$1") (pintype "bidirectional"))
      (node (ref "D23") (pin "A") (pinfunction "A_A") (pintype "bidirectional"))
      (node (ref "R67") (pin "2") (pinfunction "2_2") (pintype "passive"))
      (node (ref "U12") (pin "P$4") (pinfunction "P$4_P$4") (pintype "bidirectional"))
    )
    (net (code "61") (name "BTN7_PIN3") (class "Default")
      (node (ref "AF12") (pin "P$2") (pinfunction "P$2_P$2") (pintype "bidirectional"))
      (node (ref "D24") (pin "A") (pinfunction "A_A") (pintype "bidirectional"))
      (node (ref "R70") (pin "2") (pinfunction "2_2") (pintype "passive"))
      (node (ref "U12") (pin "P$3") (pinfunction "P$3_P$3") (pintype "bidirectional"))
    )
    (net (code "62") (name "BTN7_UP_CAP") (class "Default")
      (node (ref "C23") (pin "1") (pinfunction "1_1") (pintype "passive"))
      (node (ref "D23") (pin "K") (pinfunction "K_K") (pintype "bidirectional"))
      (node (ref "Q45") (pin "G") (pinfunction "G_G") (pintype "bidirectional"))
      (node (ref "Q46") (pin "D") (pinfunction "D_D") (pintype "bidirectional"))
    )
    (net (code "63") (name "BTN7_UP_CLR") (class "Default")
      (node (ref "JP1") (pin "15") (pinfunction "15_15") (pintype "passive"))
      (node (ref "Q46") (pin "G") (pinfunction "G_G") (pintype "bidirectional"))
      (node (ref "R69") (pin "2") (pinfunction "2_2") (pintype "passive"))
    )
    (net (code "64") (name "BTN7_UP_SENSE") (class "Default")
      (node (ref "JP1") (pin "18") (pinfunction "18_18") (pintype "passive"))
      (node (ref "Q45") (pin "D") (pinfunction "D_D") (pintype "bidirectional"))
      (node (ref "R68") (pin "1") (pinfunction "1_1") (pintype "passive"))
    )
    (net (code "65") (name "GND") (class "Default")
      (node (ref "C1") (pin "2") (pinfunction "2_2") (pintype "passive"))
      (node (ref "C10") (pin "2") (pinfunction "2_2") (pintype "passive"))
      (node (ref "C11") (pin "2") (pinfunction "2_2") (pintype "passive"))
      (node (ref "C12") (pin "2") (pinfunction "2_2") (pintype "passive"))
      (node (ref "C13") (pin "2") (pinfunction "2_2") (pintype "passive"))
      (node (ref "C14") (pin "2") (pinfunction "2_2") (pintype "passive"))
      (node (ref "C15") (pin "2") (pinfunction "2_2") (pintype "passive"))
      (node (ref "C16") (pin "2") (pinfunction "2_2") (pintype "passive"))
      (node (ref "C17") (pin "2") (pinfunction "2_2") (pintype "passive"))
      (node (ref "C18") (pin "2") (pinfunction "2_2") (pintype "passive"))
      (node (ref "C19") (pin "2") (pinfunction "2_2") (pintype "passive"))
      (node (ref "C2") (pin "2") (pinfunction "2_2") (pintype "passive"))
      (node (ref "C20") (pin "2") (pinfunction "2_2") (pintype "passive"))
      (node (ref "C21") (pin "2") (pinfunction "2_2") (pintype "passive"))
      (node (ref "C22") (pin "-") (pinfunction "-_-") (pintype "passive"))
      (node (ref "C23") (pin "2") (pinfunction "2_2") (pintype "passive"))
      (node (ref "C24") (pin "2") (pinfunction "2_2") (pintype "passive"))
      (node (ref "C25") (pin "-") (pinfunction "-_-") (pintype "passive"))
      (node (ref "C26") (pin "2") (pinfunction "2_2") (pintype "passive"))
      (node (ref "C28") (pin "2") (pinfunction "2_2") (pintype "passive"))
      (node (ref "C3") (pin "2") (pinfunction "2_2") (pintype "passive"))
      (node (ref "C4") (pin "2") (pinfunction "2_2") (pintype "passive"))
      (node (ref "C5") (pin "2") (pinfunction "2_2") (pintype "passive"))
      (node (ref "C6") (pin "2") (pinfunction "2_2") (pintype "passive"))
      (node (ref "C7") (pin "2") (pinfunction "2_2") (pintype "passive"))
      (node (ref "C8") (pin "2") (pinfunction "2_2") (pintype "passive"))
      (node (ref "C9") (pin "2") (pinfunction "2_2") (pintype "passive"))
      (node (ref "JP1") (pin "4") (pinfunction "4_4") (pintype "passive"))
      (node (ref "JP2") (pin "2") (pinfunction "2_2") (pintype "passive"))
      (node (ref "JP3") (pin "1") (pinfunction "1_1") (pintype "passive"))
      (node (ref "JP4") (pin "1") (pinfunction "1_1") (pintype "passive"))
      (node (ref "JP4") (pin "2") (pinfunction "2_2") (pintype "passive"))
      (node (ref "Q10") (pin "S") (pinfunction "S_S") (pintype "bidirectional"))
      (node (ref "Q11") (pin "S") (pinfunction "S_S") (pintype "bidirectional"))
      (node (ref "Q12") (pin "S") (pinfunction "S_S") (pintype "bidirectional"))
      (node (ref "Q13") (pin "S") (pinfunction "S_S") (pintype "bidirectional"))
      (node (ref "Q14") (pin "S") (pinfunction "S_S") (pintype "bidirectional"))
      (node (ref "Q15") (pin "S") (pinfunction "S_S") (pintype "bidirectional"))
      (node (ref "Q16") (pin "S") (pinfunction "S_S") (pintype "bidirectional"))
      (node (ref "Q17") (pin "S") (pinfunction "S_S") (pintype "bidirectional"))
      (node (ref "Q18") (pin "S") (pinfunction "S_S") (pintype "bidirectional"))
      (node (ref "Q19") (pin "S") (pinfunction "S_S") (pintype "bidirectional"))
      (node (ref "Q20") (pin "S") (pinfunction "S_S") (pintype "bidirectional"))
      (node (ref "Q21") (pin "S") (pinfunction "S_S") (pintype "bidirectional"))
      (node (ref "Q22") (pin "S") (pinfunction "S_S") (pintype "bidirectional"))
      (node (ref "Q23") (pin "S") (pinfunction "S_S") (pintype "bidirectional"))
      (node (ref "Q24") (pin "S") (pinfunction "S_S") (pintype "bidirectional"))
      (node (ref "Q29") (pin "S") (pinfunction "S_S") (pintype "bidirectional"))
      (node (ref "Q30") (pin "S") (pinfunction "S_S") (pintype "bidirectional"))
      (node (ref "Q31") (pin "S") (pinfunction "S_S") (pintype "bidirectional"))
      (node (ref "Q32") (pin "S") (pinfunction "S_S") (pintype "bidirectional"))
      (node (ref "Q37") (pin "S") (pinfunction "S_S") (pintype "bidirectional"))
      (node (ref "Q38") (pin "S") (pinfunction "S_S") (pintype "bidirectional"))
      (node (ref "Q39") (pin "S") (pinfunction "S_S") (pintype "bidirectional"))
      (node (ref "Q40") (pin "S") (pinfunction "S_S") (pintype "bidirectional"))
      (node (ref "Q45") (pin "S") (pinfunction "S_S") (pintype "bidirectional"))
      (node (ref "Q46") (pin "S") (pinfunction "S_S") (pintype "bidirectional"))
      (node (ref "Q47") (pin "S") (pinfunction "S_S") (pintype "bidirectional"))
      (node (ref "Q48") (pin "S") (pinfunction "S_S") (pintype "bidirectional"))
      (node (ref "Q5") (pin "S") (pinfunction "S_S") (pintype "bidirectional"))
      (node (ref "Q6") (pin "S") (pinfunction "S_S") (pintype "bidirectional"))
      (node (ref "Q7") (pin "S") (pinfunction "S_S") (pintype "bidirectional"))
      (node (ref "Q8") (pin "S") (pinfunction "S_S") (pintype "bidirectional"))
      (node (ref "Q9") (pin "S") (pinfunction "S_S") (pintype "bidirectional"))
      (node (ref "R10") (pin "1") (pinfunction "1_1") (pintype "passive"))
      (node (ref "R11") (pin "1") (pinfunction "1_1") (pintype "passive"))
      (node (ref "R13") (pin "1") (pinfunction "1_1") (pintype "passive"))
      (node (ref "R15") (pin "1") (pinfunction "1_1") (pintype "passive"))
      (node (ref "R16") (pin "1") (pinfunction "1_1") (pintype "passive"))
      (node (ref "R17") (pin "1") (pinfunction "1_1") (pintype "passive"))
      (node (ref "R19") (pin "1") (pinfunction "1_1") (pintype "passive"))
      (node (ref "R2") (pin "1") (pinfunction "1_1") (pintype "passive"))
      (node (ref "R21") (pin "1") (pinfunction "1_1") (pintype "passive"))
      (node (ref "R22") (pin "1") (pinfunction "1_1") (pintype "passive"))
      (node (ref "R23") (pin "1") (pinfunction "1_1") (pintype "passive"))
      (node (ref "R25") (pin "1") (pinfunction "1_1") (pintype "passive"))
      (node (ref "R27") (pin "1") (pinfunction "1_1") (pintype "passive"))
      (node (ref "R28") (pin "1") (pinfunction "1_1") (pintype "passive"))
      (node (ref "R29") (pin "1") (pinfunction "1_1") (pintype "passive"))
      (node (ref "R31") (pin "1") (pinfunction "1_1") (pintype "passive"))
      (node (ref "R33") (pin "1") (pinfunction "1_1") (pintype "passive"))
      (node (ref "R34") (pin "1") (pinfunction "1_1") (pintype "passive"))
      (node (ref "R35") (pin "1") (pinfunction "1_1") (pintype "passive"))
      (node (ref "R4") (pin "1") (pinfunction "1_1") (pintype "passive"))
      (node (ref "R43") (pin "1") (pinfunction "1_1") (pintype "passive"))
      (node (ref "R45") (pin "1") (pinfunction "1_1") (pintype "passive"))
      (node (ref "R46") (pin "1") (pinfunction "1_1") (pintype "passive"))
      (node (ref "R47") (pin "1") (pinfunction "1_1") (pintype "passive"))
      (node (ref "R55") (pin "1") (pinfunction "1_1") (pintype "passive"))
      (node (ref "R57") (pin "1") (pinfunction "1_1") (pintype "passive"))
      (node (ref "R58") (pin "1") (pinfunction "1_1") (pintype "passive"))
      (node (ref "R59") (pin "1") (pinfunction "1_1") (pintype "passive"))
      (node (ref "R67") (pin "1") (pinfunction "1_1") (pintype "passive"))
      (node (ref "R69") (pin "1") (pinfunction "1_1") (pintype "passive"))
      (node (ref "R7") (pin "1") (pinfunction "1_1") (pintype "passive"))
      (node (ref "R70") (pin "1") (pinfunction "1_1") (pintype "passive"))
      (node (ref "R71") (pin "1") (pinfunction "1_1") (pintype "passive"))
      (node (ref "R9") (pin "1") (pinfunction "1_1") (pintype "passive"))
      (node (ref "U1") (pin "2") (pinfunction "GND_2") (pintype "bidirectional"))
      (node (ref "U10") (pin "P$2") (pinfunction "P$2_P$2") (pintype "bidirectional"))
      (node (ref "U12") (pin "P$2") (pinfunction "P$2_P$2") (pintype "bidirectional"))
      (node (ref "U2") (pin "P$2") (pinfunction "P$2_P$2") (pintype "bidirectional"))
      (node (ref "U3") (pin "P$2") (pinfunction "P$2_P$2") (pintype "bidirectional"))
      (node (ref "U4") (pin "P$2") (pinfunction "P$2_P$2") (pintype "bidirectional"))
      (node (ref "U5") (pin "P$2") (pinfunction "P$2_P$2") (pintype "bidirectional"))
      (node (ref "U6") (pin "P$2") (pinfunction "P$2_P$2") (pintype "bidirectional"))
      (node (ref "U7") (pin "2") (pinfunction "GND_2") (pintype "bidirectional"))
      (node (ref "U8") (pin "P$2") (pinfunction "P$2_P$2") (pintype "bidirectional"))
    )
    (net (code "66") (name "HARVEST") (class "Default")
      (node (ref "C13") (pin "1") (pinfunction "1_1") (pintype "passive"))
      (node (ref "C14") (pin "1") (pinfunction "1_1") (pintype "passive"))
      (node (ref "C17") (pin "1") (pinfunction "1_1") (pintype "passive"))
      (node (ref "C18") (pin "1") (pinfunction "1_1") (pintype "passive"))
      (node (ref "C2") (pin "1") (pinfunction "1_1") (pintype "passive"))
      (node (ref "C21") (pin "1") (pinfunction "1_1") (pintype "passive"))
      (node (ref "C22") (pin "+") (pinfunction "+_+") (pintype "passive"))
      (node (ref "C25") (pin "+") (pinfunction "+_+") (pintype "passive"))
      (node (ref "C26") (pin "1") (pinfunction "1_1") (pintype "passive"))
      (node (ref "JP4") (pin "5") (pinfunction "5_5") (pintype "passive"))
      (node (ref "U1") (pin "1") (pinfunction "VIN_1") (pintype "bidirectional"))
      (node (ref "U1") (pin "3") (pinfunction "EN_3") (pintype "bidirectional"))
      (node (ref "U10") (pin "P$1") (pinfunction "P$1_P$1") (pintype "bidirectional"))
      (node (ref "U12") (pin "P$1") (pinfunction "P$1_P$1") (pintype "bidirectional"))
      (node (ref "U2") (pin "P$1") (pinfunction "P$1_P$1") (pintype "bidirectional"))
      (node (ref "U3") (pin "P$1") (pinfunction "P$1_P$1") (pintype "bidirectional"))
      (node (ref "U4") (pin "P$1") (pinfunction "P$1_P$1") (pintype "bidirectional"))
      (node (ref "U5") (pin "P$1") (pinfunction "P$1_P$1") (pintype "bidirectional"))
      (node (ref "U6") (pin "P$1") (pinfunction "P$1_P$1") (pintype "bidirectional"))
      (node (ref "U7") (pin "1") (pinfunction "VIN_1") (pintype "bidirectional"))
      (node (ref "U7") (pin "3") (pinfunction "EN_3") (pintype "bidirectional"))
      (node (ref "U8") (pin "P$1") (pinfunction "P$1_P$1") (pintype "bidirectional"))
    )
    (net (code "67") (name "Net-(U1-FB)") (class "Default")
      (node (ref "C27") (pin "2") (pinfunction "2_2") (pintype "passive"))
      (node (ref "R3") (pin "1") (pinfunction "1_1") (pintype "passive"))
      (node (ref "R4") (pin "2") (pinfunction "2_2") (pintype "passive"))
      (node (ref "U1") (pin "5") (pinfunction "FB_5") (pintype "bidirectional"))
    )
    (net (code "68") (name "Net-(U1-SW)") (class "Default")
      (node (ref "L1") (pin "P$1") (pinfunction "P$1_P$1") (pintype "bidirectional"))
      (node (ref "U1") (pin "7") (pinfunction "SW_7") (pintype "bidirectional"))
    )
    (net (code "69") (name "Net-(U7-NC{slash}ADJ)") (class "Default")
      (node (ref "R1") (pin "1") (pinfunction "1_1") (pintype "passive"))
      (node (ref "R2") (pin "2") (pinfunction "2_2") (pintype "passive"))
      (node (ref "U7") (pin "4") (pinfunction "NC/ADJ_4") (pintype "bidirectional"))
    )
    (net (code "70") (name "PGOOD") (class "Default")
      (node (ref "JP3") (pin "4") (pinfunction "4_4") (pintype "passive"))
      (node (ref "R5") (pin "1") (pinfunction "1_1") (pintype "passive"))
      (node (ref "U1") (pin "6") (pinfunction "PG_6") (pintype "bidirectional"))
    )
    (net (code "71") (name "VCC") (class "Default")
      (node (ref "C1") (pin "1") (pinfunction "1_1") (pintype "passive"))
      (node (ref "C27") (pin "1") (pinfunction "1_1") (pintype "passive"))
      (node (ref "C28") (pin "1") (pinfunction "1_1") (pintype "passive"))
      (node (ref "JP1") (pin "1") (pinfunction "1_1") (pintype "passive"))
      (node (ref "JP3") (pin "5") (pinfunction "5_5") (pintype "passive"))
      (node (ref "L1") (pin "P$2") (pinfunction "P$2_P$2") (pintype "bidirectional"))
      (node (ref "R1") (pin "2") (pinfunction "2_2") (pintype "passive"))
      (node (ref "R12") (pin "2") (pinfunction "2_2") (pintype "passive"))
      (node (ref "R14") (pin "2") (pinfunction "2_2") (pintype "passive"))
      (node (ref "R18") (pin "2") (pinfunction "2_2") (pintype "passive"))
      (node (ref "R20") (pin "2") (pinfunction "2_2") (pintype "passive"))
      (node (ref "R24") (pin "2") (pinfunction "2_2") (pintype "passive"))
      (node (ref "R26") (pin "2") (pinfunction "2_2") (pintype "passive"))
      (node (ref "R3") (pin "2") (pinfunction "2_2") (pintype "passive"))
      (node (ref "R30") (pin "2") (pinfunction "2_2") (pintype "passive"))
      (node (ref "R32") (pin "2") (pinfunction "2_2") (pintype "passive"))
      (node (ref "R36") (pin "2") (pinfunction "2_2") (pintype "passive"))
      (node (ref "R44") (pin "2") (pinfunction "2_2") (pintype "passive"))
      (node (ref "R48") (pin "2") (pinfunction "2_2") (pintype "passive"))
      (node (ref "R5") (pin "2") (pinfunction "2_2") (pintype "passive"))
      (node (ref "R56") (pin "2") (pinfunction "2_2") (pintype "passive"))
      (node (ref "R60") (pin "2") (pinfunction "2_2") (pintype "passive"))
      (node (ref "R68") (pin "2") (pinfunction "2_2") (pintype "passive"))
      (node (ref "R72") (pin "2") (pinfunction "2_2") (pintype "passive"))
      (node (ref "R8") (pin "2") (pinfunction "2_2") (pintype "passive"))
      (node (ref "U1") (pin "4") (pinfunction "SGND_4") (pintype "bidirectional"))
      (node (ref "U1") (pin "8") (pinfunction "VOUT_8") (pintype "bidirectional"))
      (node (ref "U7") (pin "5") (pinfunction "OUT_5") (pintype "bidirectional"))
    )
    (net (code "72") (name "unconnected-(JP1-Pad2)") (class "Default")
      (node (ref "JP1") (pin "2") (pinfunction "2_2") (pintype "passive"))
    )
    (net (code "73") (name "unconnected-(JP1-Pad13)") (class "Default")
      (node (ref "JP1") (pin "13") (pinfunction "13_13") (pintype "passive"))
    )
    (net (code "74") (name "unconnected-(JP2-Pad10)") (class "Default")
      (node (ref "JP2") (pin "10") (pinfunction "10_10") (pintype "passive"))
    )
    (net (code "75") (name "unconnected-(JP2-Pad12)") (class "Default")
      (node (ref "JP2") (pin "12") (pinfunction "12_12") (pintype "passive"))
    )
    (net (code "76") (name "unconnected-(JP2-Pad14)") (class "Default")
      (node (ref "JP2") (pin "14") (pinfunction "14_14") (pintype "passive"))
    )
    (net (code "77") (name "unconnected-(JP3-Pad2)") (class "Default")
      (node (ref "JP3") (pin "2") (pinfunction "2_2") (pintype "passive"))
    )
    (net (code "78") (name "unconnected-(JP3-Pad3)") (class "Default")
      (node (ref "JP3") (pin "3") (pinfunction "3_3") (pintype "passive"))
    )
    (net (code "79") (name "unconnected-(JP4-Pad3)") (class "Default")
      (node (ref "JP4") (pin "3") (pinfunction "3_3") (pintype "passive"))
    )
    (net (code "80") (name "unconnected-(JP4-Pad4)") (class "Default")
      (node (ref "JP4") (pin "4") (pinfunction "4_4") (pintype "passive"))
    )
  )
)
